# Embedded_System_Top.net
KiCad netlist of a schematic drawn in Altium Designer
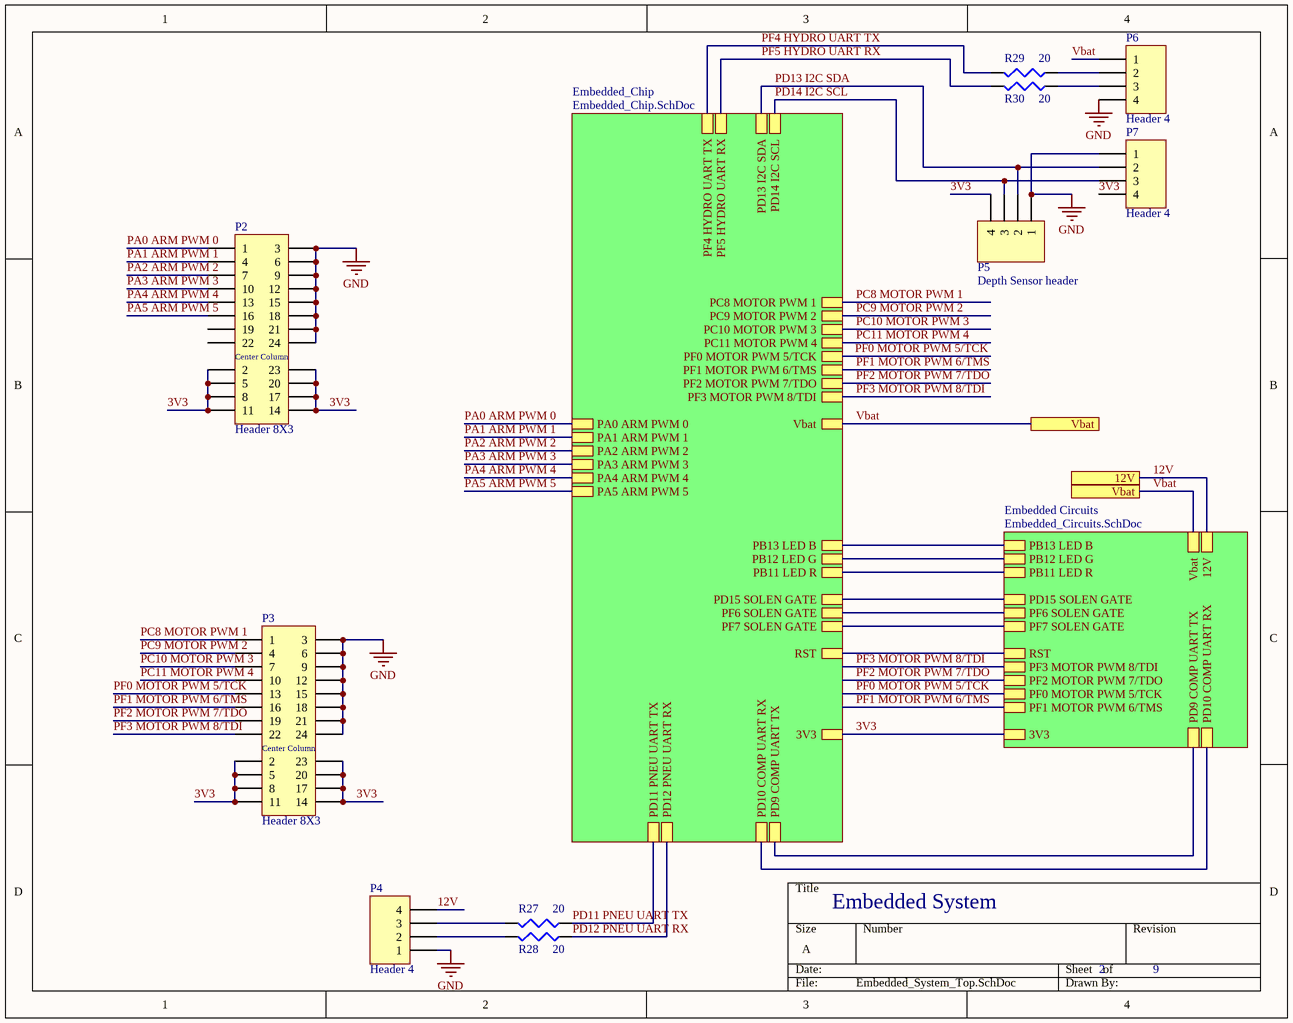
[diagram p0: Embedded_System_Top.SchDoc]

(export (version "E")
  (design (tool "Eeschema 10.0.6"))
  (components
    (comp (ref "P2")
      (value "Header 8X3")
      (footprint "Header 8X3")
      (description "Connector Header Through Hole 24 position 0.079\" (2.00mm)")
      (libsource (lib "Power_Embedded_Board_Library") (part "Header 8X3 (2mm)"))
    )
    (comp (ref "P3")
      (value "Header 8X3")
      (footprint "Header 8X3")
      (description "Connector Header Through Hole 24 position 0.079\" (2.00mm)")
      (libsource (lib "Power_Embedded_Board_Library") (part "Header 8X3 (2mm)"))
    )
    (comp (ref "P4")
      (value "Header 4")
      (footprint "Header 1x4")
      (description "Header, 4-Pin")
      (fields (field (name "PUBLISHER") "Altium Limited"))
      (libsource (lib "") (part "Header 4_1"))
    )
    (comp (ref "P5")
      (value "Depth Sensor header")
      (footprint "DF13-4P-1.25DSA")
      (description "Header, 4-Pin")
      (fields (field (name "PUBLISHER") "Altium Limited"))
      (libsource (lib "") (part "Header 4_2"))
    )
    (comp (ref "P6")
      (value "Header 4")
      (footprint "Header 1x4")
      (description "Header, 4-Pin")
      (fields (field (name "PUBLISHER") "Altium Limited"))
      (libsource (lib "Miscellaneous Connectors") (part "Header 4"))
    )
    (comp (ref "P7")
      (value "Header 4")
      (footprint "DF13-4P-1.25DSA")
      (description "Header, 4-Pin")
      (fields (field (name "PUBLISHER") "Altium Limited"))
      (libsource (lib "Miscellaneous Connectors") (part "Header 4"))
    )
    (comp (ref "R27")
      (value "20")
      (footprint "J1-0603")
      (description "Resistor")
      (fields (field (name "Comment") "Res3") (field (name "PUBLISHER") "Altium Limited"))
      (libsource (lib "Miscellaneous Devices") (part "Res3"))
    )
    (comp (ref "R28")
      (value "20")
      (footprint "J1-0603")
      (description "Resistor")
      (fields (field (name "Comment") "Res3") (field (name "PUBLISHER") "Altium Limited"))
      (libsource (lib "Miscellaneous Devices") (part "Res3"))
    )
    (comp (ref "R29")
      (value "20")
      (footprint "J1-0603")
      (description "Resistor")
      (fields (field (name "Comment") "Res3") (field (name "PUBLISHER") "Altium Limited"))
      (libsource (lib "Miscellaneous Devices") (part "Res3"))
    )
    (comp (ref "R30")
      (value "20")
      (footprint "J1-0603")
      (description "Resistor")
      (fields (field (name "Comment") "Res3") (field (name "PUBLISHER") "Altium Limited"))
      (libsource (lib "Miscellaneous Devices") (part "Res3"))
    )
  )
  (nets
    (net (code "1") (name "/3V3") (class "Default")
      (node (ref "P2") (pin "11") (pinfunction "11_11") (pintype "passive"))
      (node (ref "P2") (pin "14") (pinfunction "14_14") (pintype "passive"))
      (node (ref "P2") (pin "17") (pinfunction "17_17") (pintype "passive"))
      (node (ref "P2") (pin "2") (pinfunction "2_2") (pintype "passive"))
      (node (ref "P2") (pin "20") (pinfunction "20_20") (pintype "passive"))
      (node (ref "P2") (pin "23") (pinfunction "23_23") (pintype "passive"))
      (node (ref "P2") (pin "5") (pinfunction "5_5") (pintype "passive"))
      (node (ref "P2") (pin "8") (pinfunction "8_8") (pintype "passive"))
      (node (ref "P3") (pin "11") (pinfunction "11_11") (pintype "passive"))
      (node (ref "P3") (pin "14") (pinfunction "14_14") (pintype "passive"))
      (node (ref "P3") (pin "17") (pinfunction "17_17") (pintype "passive"))
      (node (ref "P3") (pin "2") (pinfunction "2_2") (pintype "passive"))
      (node (ref "P3") (pin "20") (pinfunction "20_20") (pintype "passive"))
      (node (ref "P3") (pin "23") (pinfunction "23_23") (pintype "passive"))
      (node (ref "P3") (pin "5") (pinfunction "5_5") (pintype "passive"))
      (node (ref "P3") (pin "8") (pinfunction "8_8") (pintype "passive"))
      (node (ref "P5") (pin "4") (pinfunction "4_4") (pintype "passive"))
      (node (ref "P7") (pin "4") (pinfunction "4_4") (pintype "passive"))
    )
    (net (code "2") (name "/12V") (class "Default")
      (node (ref "P4") (pin "4") (pinfunction "4_4") (pintype "passive"))
    )
    (net (code "3") (name "/PA0 ARM PWM 0") (class "Default")
      (node (ref "P2") (pin "1") (pinfunction "1_1") (pintype "passive"))
    )
    (net (code "4") (name "/PA1 ARM PWM 1") (class "Default")
      (node (ref "P2") (pin "4") (pinfunction "4_4") (pintype "passive"))
    )
    (net (code "5") (name "/PA2 ARM PWM 2") (class "Default")
      (node (ref "P2") (pin "7") (pinfunction "7_7") (pintype "passive"))
    )
    (net (code "6") (name "/PA3 ARM PWM 3") (class "Default")
      (node (ref "P2") (pin "10") (pinfunction "10_10") (pintype "passive"))
    )
    (net (code "7") (name "/PA4 ARM PWM 4") (class "Default")
      (node (ref "P2") (pin "13") (pinfunction "13_13") (pintype "passive"))
    )
    (net (code "8") (name "/PA5 ARM PWM 5") (class "Default")
      (node (ref "P2") (pin "16") (pinfunction "16_16") (pintype "passive"))
    )
    (net (code "12") (name "/PC8 MOTOR PWM 1") (class "Default")
      (node (ref "P3") (pin "1") (pinfunction "1_1") (pintype "passive"))
    )
    (net (code "13") (name "/PC9 MOTOR PWM 2") (class "Default")
      (node (ref "P3") (pin "4") (pinfunction "4_4") (pintype "passive"))
    )
    (net (code "14") (name "/PC10 MOTOR PWM 3") (class "Default")
      (node (ref "P3") (pin "7") (pinfunction "7_7") (pintype "passive"))
    )
    (net (code "15") (name "/PC11 MOTOR PWM 4") (class "Default")
      (node (ref "P3") (pin "10") (pinfunction "10_10") (pintype "passive"))
    )
    (net (code "18") (name "/PD11 PNEU UART TX") (class "Default")
      (node (ref "R27") (pin "1") (pinfunction "1_1") (pintype "passive"))
    )
    (net (code "19") (name "/PD12 PNEU UART RX") (class "Default")
      (node (ref "R28") (pin "1") (pinfunction "1_1") (pintype "passive"))
    )
    (net (code "20") (name "/PD13 I2C SDA") (class "Default")
      (node (ref "P5") (pin "2") (pinfunction "2_2") (pintype "passive"))
      (node (ref "P7") (pin "2") (pinfunction "2_2") (pintype "passive"))
    )
    (net (code "21") (name "/PD14 I2C SCL") (class "Default")
      (node (ref "P5") (pin "3") (pinfunction "3_3") (pintype "passive"))
      (node (ref "P7") (pin "3") (pinfunction "3_3") (pintype "passive"))
    )
    (net (code "23") (name "/PF0 MOTOR PWM 5{slash}TCK") (class "Default")
      (node (ref "P3") (pin "13") (pinfunction "13_13") (pintype "passive"))
    )
    (net (code "24") (name "/PF1 MOTOR PWM 6{slash}TMS") (class "Default")
      (node (ref "P3") (pin "16") (pinfunction "16_16") (pintype "passive"))
    )
    (net (code "25") (name "/PF2 MOTOR PWM 7{slash}TDO") (class "Default")
      (node (ref "P3") (pin "19") (pinfunction "19_19") (pintype "passive"))
    )
    (net (code "26") (name "/PF3 MOTOR PWM 8{slash}TDI") (class "Default")
      (node (ref "P3") (pin "22") (pinfunction "22_22") (pintype "passive"))
    )
    (net (code "27") (name "/PF4 HYDRO UART TX") (class "Default")
      (node (ref "R29") (pin "2") (pinfunction "2_2") (pintype "passive"))
    )
    (net (code "28") (name "/PF5 HYDRO UART RX") (class "Default")
      (node (ref "R30") (pin "2") (pinfunction "2_2") (pintype "passive"))
    )
    (net (code "32") (name "/Vbat") (class "Default")
      (node (ref "P6") (pin "1") (pinfunction "1_1") (pintype "passive"))
    )
    (net (code "33") (name "GND") (class "Default")
      (node (ref "P2") (pin "12") (pinfunction "12_12") (pintype "passive"))
      (node (ref "P2") (pin "15") (pinfunction "15_15") (pintype "passive"))
      (node (ref "P2") (pin "18") (pinfunction "18_18") (pintype "passive"))
      (node (ref "P2") (pin "21") (pinfunction "21_21") (pintype "passive"))
      (node (ref "P2") (pin "24") (pinfunction "24_24") (pintype "passive"))
      (node (ref "P2") (pin "3") (pinfunction "3_3") (pintype "passive"))
      (node (ref "P2") (pin "6") (pinfunction "6_6") (pintype "passive"))
      (node (ref "P2") (pin "9") (pinfunction "9_9") (pintype "passive"))
      (node (ref "P3") (pin "12") (pinfunction "12_12") (pintype "passive"))
      (node (ref "P3") (pin "15") (pinfunction "15_15") (pintype "passive"))
      (node (ref "P3") (pin "18") (pinfunction "18_18") (pintype "passive"))
      (node (ref "P3") (pin "21") (pinfunction "21_21") (pintype "passive"))
      (node (ref "P3") (pin "24") (pinfunction "24_24") (pintype "passive"))
      (node (ref "P3") (pin "3") (pinfunction "3_3") (pintype "passive"))
      (node (ref "P3") (pin "6") (pinfunction "6_6") (pintype "passive"))
      (node (ref "P3") (pin "9") (pinfunction "9_9") (pintype "passive"))
      (node (ref "P4") (pin "1") (pinfunction "1_1") (pintype "passive"))
      (node (ref "P5") (pin "1") (pinfunction "1_1") (pintype "passive"))
      (node (ref "P6") (pin "4") (pinfunction "4_4") (pintype "passive"))
      (node (ref "P7") (pin "1") (pinfunction "1_1") (pintype "passive"))
    )
    (net (code "34") (name "Net-(P4-Pad2)") (class "Default")
      (node (ref "P4") (pin "2") (pinfunction "2_2") (pintype "passive"))
      (node (ref "R28") (pin "2") (pinfunction "2_2") (pintype "passive"))
    )
    (net (code "35") (name "Net-(P4-Pad3)") (class "Default")
      (node (ref "P4") (pin "3") (pinfunction "3_3") (pintype "passive"))
      (node (ref "R27") (pin "2") (pinfunction "2_2") (pintype "passive"))
    )
    (net (code "36") (name "Net-(P6-Pad2)") (class "Default")
      (node (ref "P6") (pin "2") (pinfunction "2_2") (pintype "passive"))
      (node (ref "R29") (pin "1") (pinfunction "1_1") (pintype "passive"))
    )
    (net (code "37") (name "Net-(P6-Pad3)") (class "Default")
      (node (ref "P6") (pin "3") (pinfunction "3_3") (pintype "passive"))
      (node (ref "R30") (pin "1") (pinfunction "1_1") (pintype "passive"))
    )
    (net (code "38") (name "unconnected-(P2-Pad19)") (class "Default")
      (node (ref "P2") (pin "19") (pinfunction "19_19") (pintype "passive"))
    )
    (net (code "39") (name "unconnected-(P2-Pad22)") (class "Default")
      (node (ref "P2") (pin "22") (pinfunction "22_22") (pintype "passive"))
    )
  )
)
